# rotaryswitchencoder.net
KiCad netlist of a schematic drawn in EAGLE
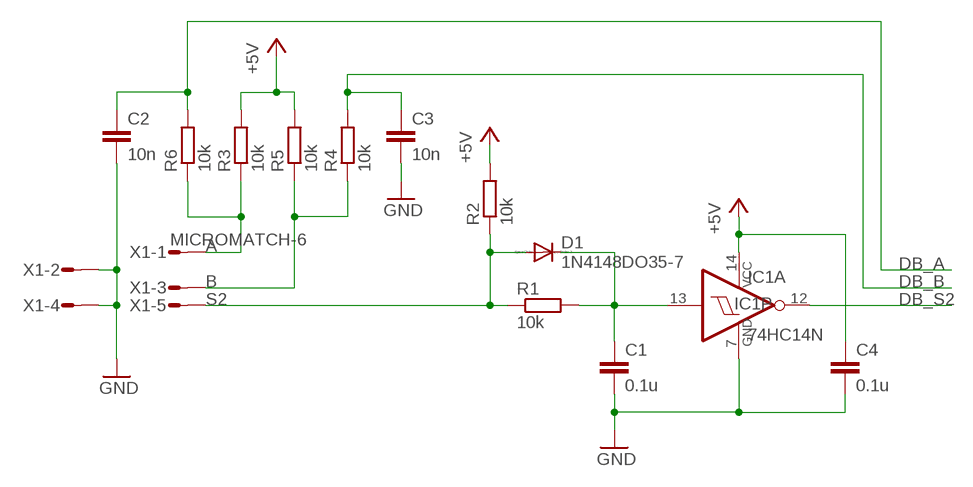
[diagram p0: schematic, sheet 1]

(export (version "E")
  (design (tool "Eeschema 10.0.6"))
  (components
    (comp (ref "C1")
      (value "0.1u")
      (footprint "eagle-import:C050-024X044")
      (libsource (lib "eagle-import") (part "C-EU050-024X044"))
    )
    (comp (ref "C2")
      (value "10n")
      (footprint "eagle-import:C050-024X044")
      (libsource (lib "eagle-import") (part "C-EU050-024X044"))
    )
    (comp (ref "C3")
      (value "10n")
      (footprint "eagle-import:C050-024X044")
      (libsource (lib "eagle-import") (part "C-EU050-024X044"))
    )
    (comp (ref "C4")
      (value "0.1u")
      (footprint "eagle-import:C050-024X044")
      (libsource (lib "eagle-import") (part "C-EU050-024X044"))
    )
    (comp (ref "D1")
      (value "1N4148DO35-7")
      (footprint "eagle-import:DO35-7")
      (libsource (lib "eagle-import") (part "1N4148DO35-7"))
    )
    (comp (ref "IC1")
      (value "74HC14N")
      (footprint "eagle-import:DIL14")
      (libsource (lib "eagle-import") (part "7414NHC"))
    )
    (comp (ref "R1")
      (value "10k")
      (footprint "eagle-import:0204_7")
      (libsource (lib "eagle-import") (part "R-EU_0204/7"))
    )
    (comp (ref "R2")
      (value "10k")
      (footprint "eagle-import:0204_7")
      (libsource (lib "eagle-import") (part "R-EU_0204/7"))
    )
    (comp (ref "R3")
      (value "10k")
      (footprint "eagle-import:0204_7")
      (libsource (lib "eagle-import") (part "R-EU_0204/7"))
    )
    (comp (ref "R4")
      (value "10k")
      (footprint "eagle-import:0204_7")
      (libsource (lib "eagle-import") (part "R-EU_0204/7"))
    )
    (comp (ref "R5")
      (value "10k")
      (footprint "eagle-import:0204_7")
      (libsource (lib "eagle-import") (part "R-EU_0204/7"))
    )
    (comp (ref "R6")
      (value "10k")
      (footprint "eagle-import:0204_7")
      (libsource (lib "eagle-import") (part "R-EU_0204/7"))
    )
    (comp (ref "X1")
      (value "MICROMATCH-6")
      (footprint "eagle-import:MICROMATCH-6")
      (fields (field (name "MPN") "7-215464-6"))
      (libsource (lib "eagle-import") (part "MICROMATCH-6"))
    )
  )
  (nets
    (net (code "1") (name "+5V") (class "Default")
      (node (ref "C4") (pin "1") (pinfunction "1_1") (pintype "passive"))
      (node (ref "IC1") (pin "14") (pinfunction "VCC_14") (pintype "power_in"))
      (node (ref "R2") (pin "2") (pinfunction "2_2") (pintype "passive"))
      (node (ref "R3") (pin "2") (pinfunction "2_2") (pintype "passive"))
      (node (ref "R5") (pin "2") (pinfunction "2_2") (pintype "passive"))
    )
    (net (code "2") (name "/A") (class "Default")
      (node (ref "R3") (pin "1") (pinfunction "1_1") (pintype "passive"))
      (node (ref "R6") (pin "1") (pinfunction "1_1") (pintype "passive"))
      (node (ref "X1") (pin "1") (pinfunction "S_1") (pintype "passive"))
    )
    (net (code "3") (name "/B") (class "Default")
      (node (ref "R4") (pin "1") (pinfunction "1_1") (pintype "passive"))
      (node (ref "R5") (pin "1") (pinfunction "1_1") (pintype "passive"))
      (node (ref "X1") (pin "3") (pinfunction "S_3") (pintype "passive"))
    )
    (net (code "4") (name "/DB_A") (class "Default")
      (node (ref "C2") (pin "1") (pinfunction "1_1") (pintype "passive"))
      (node (ref "R6") (pin "2") (pinfunction "2_2") (pintype "passive"))
    )
    (net (code "5") (name "/DB_B") (class "Default")
      (node (ref "C3") (pin "1") (pinfunction "1_1") (pintype "passive"))
      (node (ref "R4") (pin "2") (pinfunction "2_2") (pintype "passive"))
    )
    (net (code "6") (name "/DB_S2") (class "Default")
      (node (ref "IC1") (pin "12") (pinfunction "O_12") (pintype "output"))
    )
    (net (code "7") (name "/S2") (class "Default")
      (node (ref "D1") (pin "A") (pinfunction "A_A") (pintype "passive"))
      (node (ref "R1") (pin "1") (pinfunction "1_1") (pintype "passive"))
      (node (ref "R2") (pin "1") (pinfunction "1_1") (pintype "passive"))
      (node (ref "X1") (pin "5") (pinfunction "S_5") (pintype "passive"))
    )
    (net (code "8") (name "GND") (class "Default")
      (node (ref "C1") (pin "2") (pinfunction "2_2") (pintype "passive"))
      (node (ref "C2") (pin "2") (pinfunction "2_2") (pintype "passive"))
      (node (ref "C3") (pin "2") (pinfunction "2_2") (pintype "passive"))
      (node (ref "C4") (pin "2") (pinfunction "2_2") (pintype "passive"))
      (node (ref "IC1") (pin "7") (pinfunction "GND_7") (pintype "power_in"))
      (node (ref "X1") (pin "2") (pinfunction "S_2") (pintype "passive"))
      (node (ref "X1") (pin "4") (pinfunction "S_4") (pintype "passive"))
    )
    (net (code "9") (name "Net-(IC1A-I)") (class "Default")
      (node (ref "C1") (pin "1") (pinfunction "1_1") (pintype "passive"))
      (node (ref "D1") (pin "C") (pinfunction "C_C") (pintype "passive"))
      (node (ref "IC1") (pin "13") (pinfunction "I_13") (pintype "input"))
      (node (ref "R1") (pin "2") (pinfunction "2_2") (pintype "passive"))
    )
  )
)
